# 7segmentDisplay.net
KiCad netlist of a schematic drawn in EAGLE
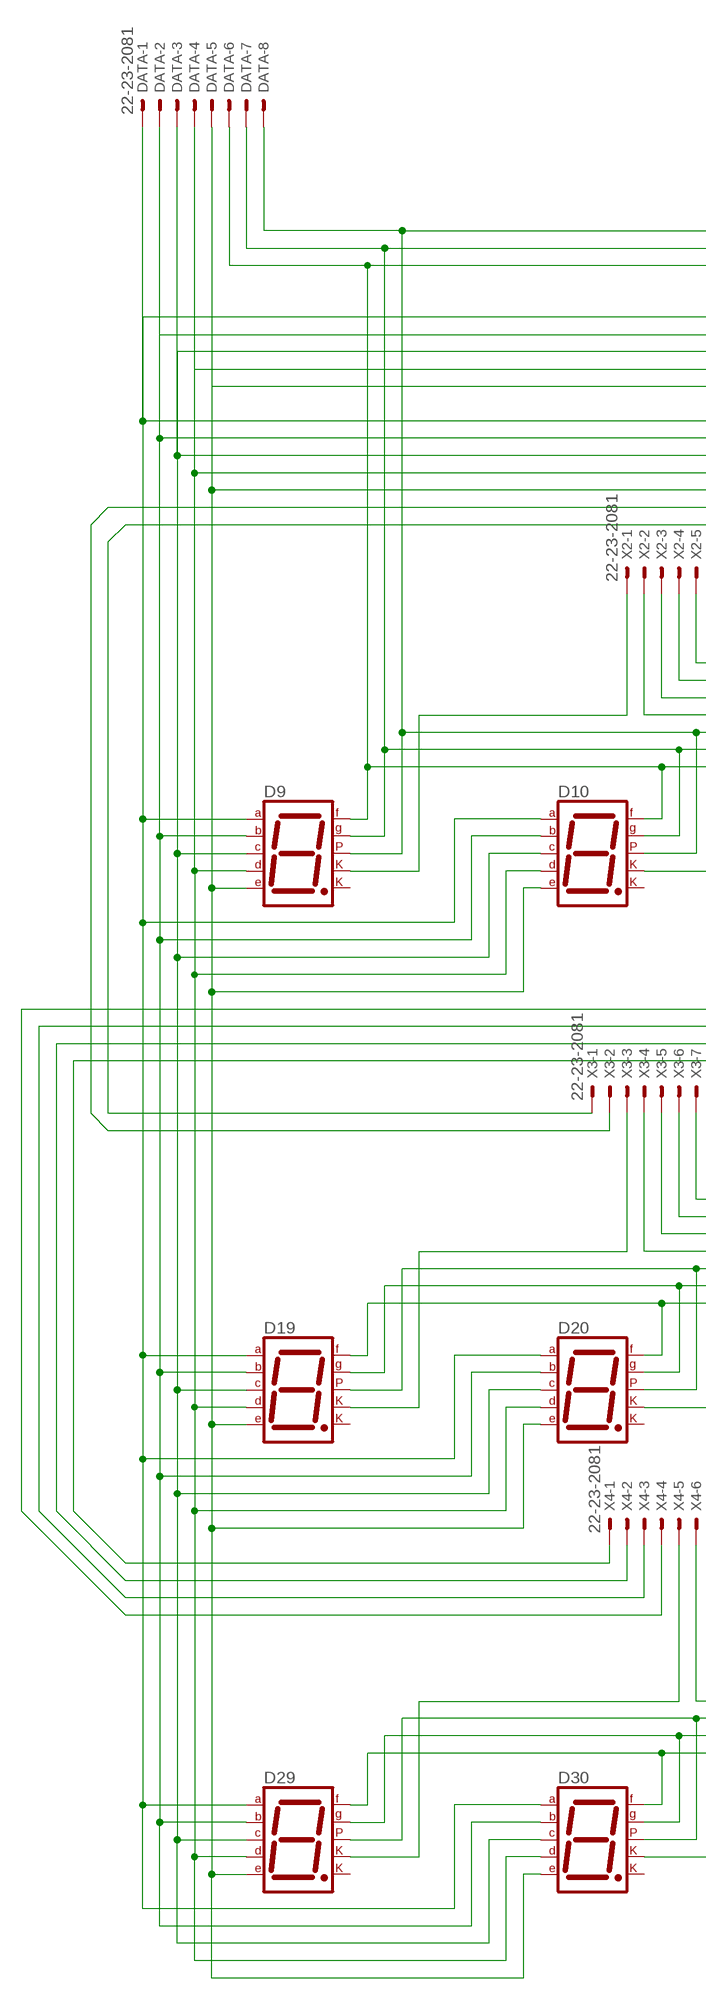
[diagram p0: schematic, sheet 1, part 1 of 2]
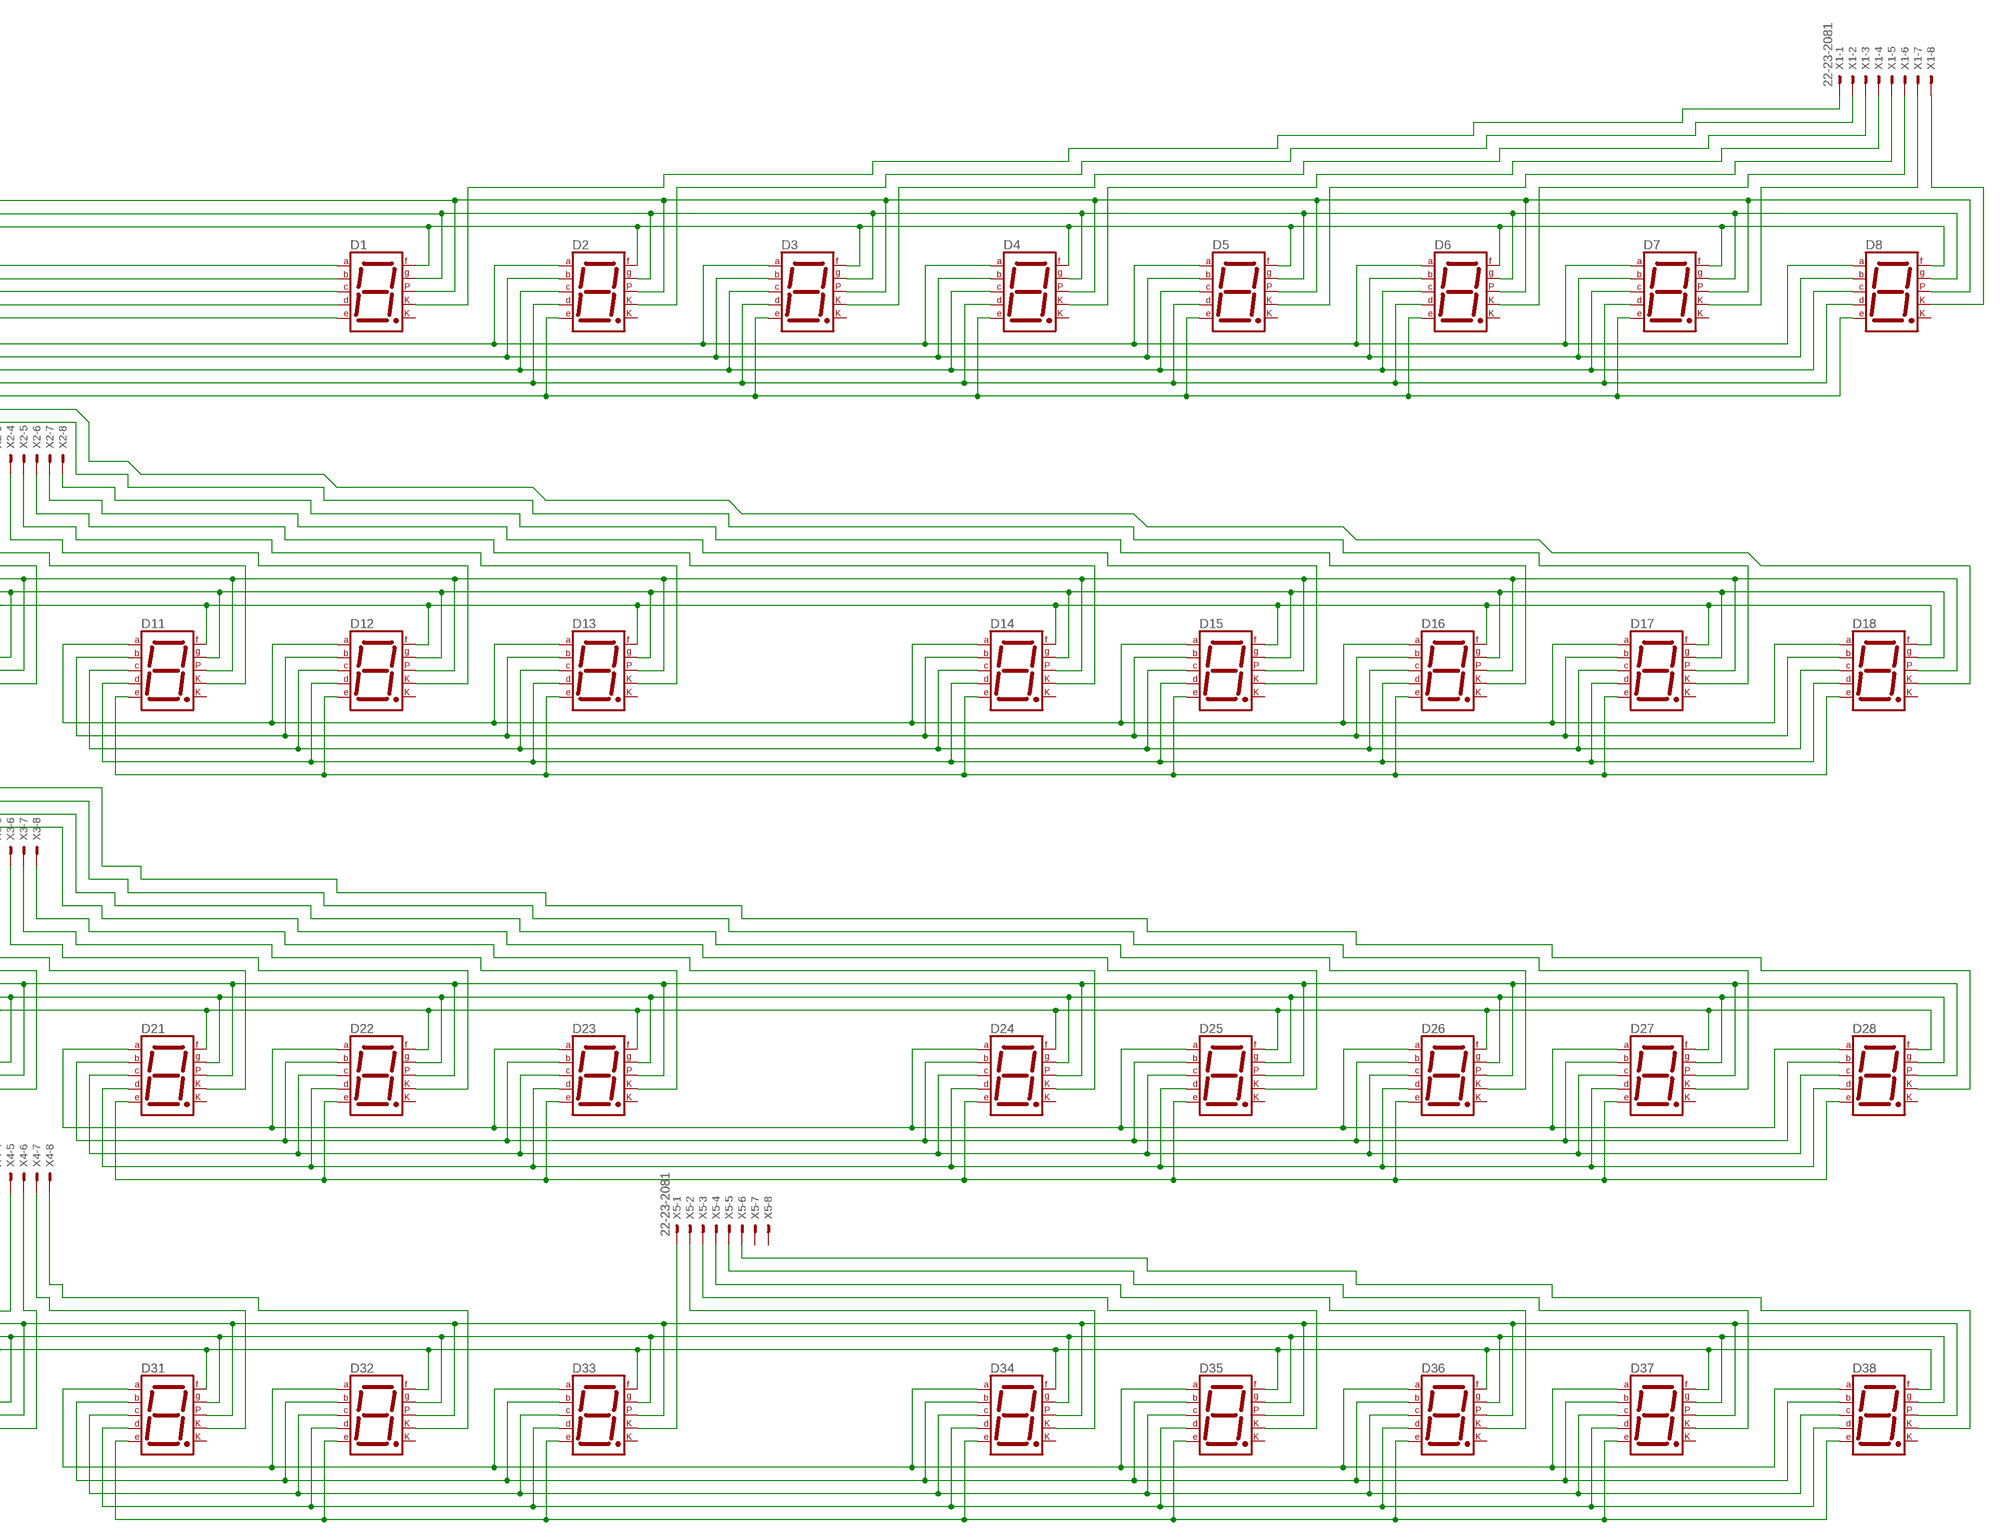
[diagram p1: schematic, sheet 1, part 2 of 2]

(export (version "E")
  (design (tool "Eeschema 10.0.6"))
  (components
    (comp (ref "D1")
      (value "7SEG-CK")
      (footprint "eagle-import:7SEG-13")
      (libsource (lib "eagle-import") (part "7SEG-CK"))
    )
    (comp (ref "D2")
      (value "7SEG-CK")
      (footprint "eagle-import:7SEG-13")
      (libsource (lib "eagle-import") (part "7SEG-CK"))
    )
    (comp (ref "D3")
      (value "7SEG-CK")
      (footprint "eagle-import:7SEG-13")
      (libsource (lib "eagle-import") (part "7SEG-CK"))
    )
    (comp (ref "D4")
      (value "7SEG-CK")
      (footprint "eagle-import:7SEG-13")
      (libsource (lib "eagle-import") (part "7SEG-CK"))
    )
    (comp (ref "D5")
      (value "7SEG-CK")
      (footprint "eagle-import:7SEG-13")
      (libsource (lib "eagle-import") (part "7SEG-CK"))
    )
    (comp (ref "D6")
      (value "7SEG-CK")
      (footprint "eagle-import:7SEG-13")
      (libsource (lib "eagle-import") (part "7SEG-CK"))
    )
    (comp (ref "D7")
      (value "7SEG-CK")
      (footprint "eagle-import:7SEG-13")
      (libsource (lib "eagle-import") (part "7SEG-CK"))
    )
    (comp (ref "D8")
      (value "7SEG-CK")
      (footprint "eagle-import:7SEG-13")
      (libsource (lib "eagle-import") (part "7SEG-CK"))
    )
    (comp (ref "D9")
      (value "7SEG-CK")
      (footprint "eagle-import:7SEG-13")
      (libsource (lib "eagle-import") (part "7SEG-CK"))
    )
    (comp (ref "D10")
      (value "7SEG-CK")
      (footprint "eagle-import:7SEG-13")
      (libsource (lib "eagle-import") (part "7SEG-CK"))
    )
    (comp (ref "D11")
      (value "7SEG-CK")
      (footprint "eagle-import:7SEG-13")
      (libsource (lib "eagle-import") (part "7SEG-CK"))
    )
    (comp (ref "D12")
      (value "7SEG-CK")
      (footprint "eagle-import:7SEG-13")
      (libsource (lib "eagle-import") (part "7SEG-CK"))
    )
    (comp (ref "D13")
      (value "7SEG-CK")
      (footprint "eagle-import:7SEG-13")
      (libsource (lib "eagle-import") (part "7SEG-CK"))
    )
    (comp (ref "D14")
      (value "7SEG-CK")
      (footprint "eagle-import:7SEG-13")
      (libsource (lib "eagle-import") (part "7SEG-CK"))
    )
    (comp (ref "D15")
      (value "7SEG-CK")
      (footprint "eagle-import:7SEG-13")
      (libsource (lib "eagle-import") (part "7SEG-CK"))
    )
    (comp (ref "D16")
      (value "7SEG-CK")
      (footprint "eagle-import:7SEG-13")
      (libsource (lib "eagle-import") (part "7SEG-CK"))
    )
    (comp (ref "D17")
      (value "7SEG-CK")
      (footprint "eagle-import:7SEG-13")
      (libsource (lib "eagle-import") (part "7SEG-CK"))
    )
    (comp (ref "D18")
      (value "7SEG-CK")
      (footprint "eagle-import:7SEG-13")
      (libsource (lib "eagle-import") (part "7SEG-CK"))
    )
    (comp (ref "D19")
      (value "7SEG-CK")
      (footprint "eagle-import:7SEG-13")
      (libsource (lib "eagle-import") (part "7SEG-CK"))
    )
    (comp (ref "D20")
      (value "7SEG-CK")
      (footprint "eagle-import:7SEG-13")
      (libsource (lib "eagle-import") (part "7SEG-CK"))
    )
    (comp (ref "D21")
      (value "7SEG-CK")
      (footprint "eagle-import:7SEG-13")
      (libsource (lib "eagle-import") (part "7SEG-CK"))
    )
    (comp (ref "D22")
      (value "7SEG-CK")
      (footprint "eagle-import:7SEG-13")
      (libsource (lib "eagle-import") (part "7SEG-CK"))
    )
    (comp (ref "D23")
      (value "7SEG-CK")
      (footprint "eagle-import:7SEG-13")
      (libsource (lib "eagle-import") (part "7SEG-CK"))
    )
    (comp (ref "D24")
      (value "7SEG-CK")
      (footprint "eagle-import:7SEG-13")
      (libsource (lib "eagle-import") (part "7SEG-CK"))
    )
    (comp (ref "D25")
      (value "7SEG-CK")
      (footprint "eagle-import:7SEG-13")
      (libsource (lib "eagle-import") (part "7SEG-CK"))
    )
    (comp (ref "D26")
      (value "7SEG-CK")
      (footprint "eagle-import:7SEG-13")
      (libsource (lib "eagle-import") (part "7SEG-CK"))
    )
    (comp (ref "D27")
      (value "7SEG-CK")
      (footprint "eagle-import:7SEG-13")
      (libsource (lib "eagle-import") (part "7SEG-CK"))
    )
    (comp (ref "D28")
      (value "7SEG-CK")
      (footprint "eagle-import:7SEG-13")
      (libsource (lib "eagle-import") (part "7SEG-CK"))
    )
    (comp (ref "D29")
      (value "7SEG-CK")
      (footprint "eagle-import:7SEG-13")
      (libsource (lib "eagle-import") (part "7SEG-CK"))
    )
    (comp (ref "D30")
      (value "7SEG-CK")
      (footprint "eagle-import:7SEG-13")
      (libsource (lib "eagle-import") (part "7SEG-CK"))
    )
    (comp (ref "D31")
      (value "7SEG-CK")
      (footprint "eagle-import:7SEG-13")
      (libsource (lib "eagle-import") (part "7SEG-CK"))
    )
    (comp (ref "D32")
      (value "7SEG-CK")
      (footprint "eagle-import:7SEG-13")
      (libsource (lib "eagle-import") (part "7SEG-CK"))
    )
    (comp (ref "D33")
      (value "7SEG-CK")
      (footprint "eagle-import:7SEG-13")
      (libsource (lib "eagle-import") (part "7SEG-CK"))
    )
    (comp (ref "D34")
      (value "7SEG-CK")
      (footprint "eagle-import:7SEG-13")
      (libsource (lib "eagle-import") (part "7SEG-CK"))
    )
    (comp (ref "D35")
      (value "7SEG-CK")
      (footprint "eagle-import:7SEG-13")
      (libsource (lib "eagle-import") (part "7SEG-CK"))
    )
    (comp (ref "D36")
      (value "7SEG-CK")
      (footprint "eagle-import:7SEG-13")
      (libsource (lib "eagle-import") (part "7SEG-CK"))
    )
    (comp (ref "D37")
      (value "7SEG-CK")
      (footprint "eagle-import:7SEG-13")
      (libsource (lib "eagle-import") (part "7SEG-CK"))
    )
    (comp (ref "D38")
      (value "7SEG-CK")
      (footprint "eagle-import:7SEG-13")
      (libsource (lib "eagle-import") (part "7SEG-CK"))
    )
    (comp (ref "DATA")
      (value "22-23-2081")
      (footprint "eagle-import:22-23-2081")
      (fields (field (name "MF") "MOLEX"))
      (libsource (lib "eagle-import") (part "22-23-2081"))
    )
    (comp (ref "X1")
      (value "22-23-2081")
      (footprint "eagle-import:22-23-2081")
      (fields (field (name "MF") "MOLEX"))
      (libsource (lib "eagle-import") (part "22-23-2081"))
    )
    (comp (ref "X2")
      (value "22-23-2081")
      (footprint "eagle-import:22-23-2081")
      (fields (field (name "MF") "MOLEX"))
      (libsource (lib "eagle-import") (part "22-23-2081"))
    )
    (comp (ref "X3")
      (value "22-23-2081")
      (footprint "eagle-import:22-23-2081")
      (fields (field (name "MF") "MOLEX"))
      (libsource (lib "eagle-import") (part "22-23-2081"))
    )
    (comp (ref "X4")
      (value "22-23-2081")
      (footprint "eagle-import:22-23-2081")
      (fields (field (name "MF") "MOLEX"))
      (libsource (lib "eagle-import") (part "22-23-2081"))
    )
    (comp (ref "X5")
      (value "22-23-2081")
      (footprint "eagle-import:22-23-2081")
      (fields (field (name "MF") "MOLEX"))
      (libsource (lib "eagle-import") (part "22-23-2081"))
    )
  )
  (nets
    (net (code "1") (name "Net-(D1-A)") (class "Default")
      (node (ref "D1") (pin "7") (pinfunction "A_7") (pintype "passive"))
      (node (ref "D10") (pin "7") (pinfunction "A_7") (pintype "passive"))
      (node (ref "D19") (pin "7") (pinfunction "A_7") (pintype "passive"))
      (node (ref "D2") (pin "7") (pinfunction "A_7") (pintype "passive"))
      (node (ref "D20") (pin "7") (pinfunction "A_7") (pintype "passive"))
      (node (ref "D29") (pin "7") (pinfunction "A_7") (pintype "passive"))
      (node (ref "D3") (pin "7") (pinfunction "A_7") (pintype "passive"))
      (node (ref "D30") (pin "7") (pinfunction "A_7") (pintype "passive"))
      (node (ref "D4") (pin "7") (pinfunction "A_7") (pintype "passive"))
      (node (ref "D5") (pin "7") (pinfunction "A_7") (pintype "passive"))
      (node (ref "D6") (pin "7") (pinfunction "A_7") (pintype "passive"))
      (node (ref "D7") (pin "7") (pinfunction "A_7") (pintype "passive"))
      (node (ref "D8") (pin "7") (pinfunction "A_7") (pintype "passive"))
      (node (ref "D9") (pin "7") (pinfunction "A_7") (pintype "passive"))
      (node (ref "DATA") (pin "1") (pinfunction "S_1") (pintype "passive"))
    )
    (net (code "2") (name "Net-(D1-B)") (class "Default")
      (node (ref "D1") (pin "6") (pinfunction "B_6") (pintype "passive"))
      (node (ref "D10") (pin "6") (pinfunction "B_6") (pintype "passive"))
      (node (ref "D19") (pin "6") (pinfunction "B_6") (pintype "passive"))
      (node (ref "D2") (pin "6") (pinfunction "B_6") (pintype "passive"))
      (node (ref "D20") (pin "6") (pinfunction "B_6") (pintype "passive"))
      (node (ref "D29") (pin "6") (pinfunction "B_6") (pintype "passive"))
      (node (ref "D3") (pin "6") (pinfunction "B_6") (pintype "passive"))
      (node (ref "D30") (pin "6") (pinfunction "B_6") (pintype "passive"))
      (node (ref "D4") (pin "6") (pinfunction "B_6") (pintype "passive"))
      (node (ref "D5") (pin "6") (pinfunction "B_6") (pintype "passive"))
      (node (ref "D6") (pin "6") (pinfunction "B_6") (pintype "passive"))
      (node (ref "D7") (pin "6") (pinfunction "B_6") (pintype "passive"))
      (node (ref "D8") (pin "6") (pinfunction "B_6") (pintype "passive"))
      (node (ref "D9") (pin "6") (pinfunction "B_6") (pintype "passive"))
      (node (ref "DATA") (pin "2") (pinfunction "S_2") (pintype "passive"))
    )
    (net (code "3") (name "Net-(D1-C)") (class "Default")
      (node (ref "D1") (pin "4") (pinfunction "C_4") (pintype "passive"))
      (node (ref "D10") (pin "4") (pinfunction "C_4") (pintype "passive"))
      (node (ref "D19") (pin "4") (pinfunction "C_4") (pintype "passive"))
      (node (ref "D2") (pin "4") (pinfunction "C_4") (pintype "passive"))
      (node (ref "D20") (pin "4") (pinfunction "C_4") (pintype "passive"))
      (node (ref "D29") (pin "4") (pinfunction "C_4") (pintype "passive"))
      (node (ref "D3") (pin "4") (pinfunction "C_4") (pintype "passive"))
      (node (ref "D30") (pin "4") (pinfunction "C_4") (pintype "passive"))
      (node (ref "D4") (pin "4") (pinfunction "C_4") (pintype "passive"))
      (node (ref "D5") (pin "4") (pinfunction "C_4") (pintype "passive"))
      (node (ref "D6") (pin "4") (pinfunction "C_4") (pintype "passive"))
      (node (ref "D7") (pin "4") (pinfunction "C_4") (pintype "passive"))
      (node (ref "D8") (pin "4") (pinfunction "C_4") (pintype "passive"))
      (node (ref "D9") (pin "4") (pinfunction "C_4") (pintype "passive"))
      (node (ref "DATA") (pin "3") (pinfunction "S_3") (pintype "passive"))
    )
    (net (code "4") (name "Net-(D1-CK1)") (class "Default")
      (node (ref "D1") (pin "3") (pinfunction "CK1_3") (pintype "passive"))
      (node (ref "X1") (pin "1") (pinfunction "S_1") (pintype "passive"))
    )
    (net (code "5") (name "Net-(D1-D)") (class "Default")
      (node (ref "D1") (pin "2") (pinfunction "D_2") (pintype "passive"))
      (node (ref "D10") (pin "2") (pinfunction "D_2") (pintype "passive"))
      (node (ref "D19") (pin "2") (pinfunction "D_2") (pintype "passive"))
      (node (ref "D2") (pin "2") (pinfunction "D_2") (pintype "passive"))
      (node (ref "D20") (pin "2") (pinfunction "D_2") (pintype "passive"))
      (node (ref "D29") (pin "2") (pinfunction "D_2") (pintype "passive"))
      (node (ref "D3") (pin "2") (pinfunction "D_2") (pintype "passive"))
      (node (ref "D30") (pin "2") (pinfunction "D_2") (pintype "passive"))
      (node (ref "D4") (pin "2") (pinfunction "D_2") (pintype "passive"))
      (node (ref "D5") (pin "2") (pinfunction "D_2") (pintype "passive"))
      (node (ref "D6") (pin "2") (pinfunction "D_2") (pintype "passive"))
      (node (ref "D7") (pin "2") (pinfunction "D_2") (pintype "passive"))
      (node (ref "D8") (pin "2") (pinfunction "D_2") (pintype "passive"))
      (node (ref "D9") (pin "2") (pinfunction "D_2") (pintype "passive"))
      (node (ref "DATA") (pin "4") (pinfunction "S_4") (pintype "passive"))
    )
    (net (code "6") (name "Net-(D1-DP)") (class "Default")
      (node (ref "D1") (pin "5") (pinfunction "DP_5") (pintype "passive"))
      (node (ref "D10") (pin "5") (pinfunction "DP_5") (pintype "passive"))
      (node (ref "D11") (pin "5") (pinfunction "DP_5") (pintype "passive"))
      (node (ref "D12") (pin "5") (pinfunction "DP_5") (pintype "passive"))
      (node (ref "D13") (pin "5") (pinfunction "DP_5") (pintype "passive"))
      (node (ref "D14") (pin "5") (pinfunction "DP_5") (pintype "passive"))
      (node (ref "D15") (pin "5") (pinfunction "DP_5") (pintype "passive"))
      (node (ref "D16") (pin "5") (pinfunction "DP_5") (pintype "passive"))
      (node (ref "D17") (pin "5") (pinfunction "DP_5") (pintype "passive"))
      (node (ref "D18") (pin "5") (pinfunction "DP_5") (pintype "passive"))
      (node (ref "D2") (pin "5") (pinfunction "DP_5") (pintype "passive"))
      (node (ref "D3") (pin "5") (pinfunction "DP_5") (pintype "passive"))
      (node (ref "D4") (pin "5") (pinfunction "DP_5") (pintype "passive"))
      (node (ref "D5") (pin "5") (pinfunction "DP_5") (pintype "passive"))
      (node (ref "D6") (pin "5") (pinfunction "DP_5") (pintype "passive"))
      (node (ref "D7") (pin "5") (pinfunction "DP_5") (pintype "passive"))
      (node (ref "D8") (pin "5") (pinfunction "DP_5") (pintype "passive"))
      (node (ref "D9") (pin "5") (pinfunction "DP_5") (pintype "passive"))
      (node (ref "DATA") (pin "8") (pinfunction "S_8") (pintype "passive"))
    )
    (net (code "7") (name "Net-(D1-E)") (class "Default")
      (node (ref "D1") (pin "1") (pinfunction "E_1") (pintype "passive"))
      (node (ref "D10") (pin "1") (pinfunction "E_1") (pintype "passive"))
      (node (ref "D19") (pin "1") (pinfunction "E_1") (pintype "passive"))
      (node (ref "D2") (pin "1") (pinfunction "E_1") (pintype "passive"))
      (node (ref "D20") (pin "1") (pinfunction "E_1") (pintype "passive"))
      (node (ref "D29") (pin "1") (pinfunction "E_1") (pintype "passive"))
      (node (ref "D3") (pin "1") (pinfunction "E_1") (pintype "passive"))
      (node (ref "D30") (pin "1") (pinfunction "E_1") (pintype "passive"))
      (node (ref "D4") (pin "1") (pinfunction "E_1") (pintype "passive"))
      (node (ref "D5") (pin "1") (pinfunction "E_1") (pintype "passive"))
      (node (ref "D6") (pin "1") (pinfunction "E_1") (pintype "passive"))
      (node (ref "D7") (pin "1") (pinfunction "E_1") (pintype "passive"))
      (node (ref "D8") (pin "1") (pinfunction "E_1") (pintype "passive"))
      (node (ref "D9") (pin "1") (pinfunction "E_1") (pintype "passive"))
      (node (ref "DATA") (pin "5") (pinfunction "S_5") (pintype "passive"))
    )
    (net (code "8") (name "Net-(D1-F)") (class "Default")
      (node (ref "D1") (pin "9") (pinfunction "F_9") (pintype "passive"))
      (node (ref "D10") (pin "9") (pinfunction "F_9") (pintype "passive"))
      (node (ref "D11") (pin "9") (pinfunction "F_9") (pintype "passive"))
      (node (ref "D12") (pin "9") (pinfunction "F_9") (pintype "passive"))
      (node (ref "D13") (pin "9") (pinfunction "F_9") (pintype "passive"))
      (node (ref "D14") (pin "9") (pinfunction "F_9") (pintype "passive"))
      (node (ref "D15") (pin "9") (pinfunction "F_9") (pintype "passive"))
      (node (ref "D16") (pin "9") (pinfunction "F_9") (pintype "passive"))
      (node (ref "D17") (pin "9") (pinfunction "F_9") (pintype "passive"))
      (node (ref "D18") (pin "9") (pinfunction "F_9") (pintype "passive"))
      (node (ref "D2") (pin "9") (pinfunction "F_9") (pintype "passive"))
      (node (ref "D3") (pin "9") (pinfunction "F_9") (pintype "passive"))
      (node (ref "D4") (pin "9") (pinfunction "F_9") (pintype "passive"))
      (node (ref "D5") (pin "9") (pinfunction "F_9") (pintype "passive"))
      (node (ref "D6") (pin "9") (pinfunction "F_9") (pintype "passive"))
      (node (ref "D7") (pin "9") (pinfunction "F_9") (pintype "passive"))
      (node (ref "D8") (pin "9") (pinfunction "F_9") (pintype "passive"))
      (node (ref "D9") (pin "9") (pinfunction "F_9") (pintype "passive"))
      (node (ref "DATA") (pin "6") (pinfunction "S_6") (pintype "passive"))
    )
    (net (code "9") (name "Net-(D1-G)") (class "Default")
      (node (ref "D1") (pin "10") (pinfunction "G_10") (pintype "passive"))
      (node (ref "D10") (pin "10") (pinfunction "G_10") (pintype "passive"))
      (node (ref "D11") (pin "10") (pinfunction "G_10") (pintype "passive"))
      (node (ref "D12") (pin "10") (pinfunction "G_10") (pintype "passive"))
      (node (ref "D13") (pin "10") (pinfunction "G_10") (pintype "passive"))
      (node (ref "D2") (pin "10") (pinfunction "G_10") (pintype "passive"))
      (node (ref "D3") (pin "10") (pinfunction "G_10") (pintype "passive"))
      (node (ref "D4") (pin "10") (pinfunction "G_10") (pintype "passive"))
      (node (ref "D5") (pin "10") (pinfunction "G_10") (pintype "passive"))
      (node (ref "D6") (pin "10") (pinfunction "G_10") (pintype "passive"))
      (node (ref "D7") (pin "10") (pinfunction "G_10") (pintype "passive"))
      (node (ref "D8") (pin "10") (pinfunction "G_10") (pintype "passive"))
      (node (ref "D9") (pin "10") (pinfunction "G_10") (pintype "passive"))
      (node (ref "DATA") (pin "7") (pinfunction "S_7") (pintype "passive"))
    )
    (net (code "10") (name "Net-(D2-CK1)") (class "Default")
      (node (ref "D2") (pin "3") (pinfunction "CK1_3") (pintype "passive"))
      (node (ref "X1") (pin "2") (pinfunction "S_2") (pintype "passive"))
    )
    (net (code "11") (name "Net-(D3-CK1)") (class "Default")
      (node (ref "D3") (pin "3") (pinfunction "CK1_3") (pintype "passive"))
      (node (ref "X1") (pin "3") (pinfunction "S_3") (pintype "passive"))
    )
    (net (code "12") (name "Net-(D4-CK1)") (class "Default")
      (node (ref "D4") (pin "3") (pinfunction "CK1_3") (pintype "passive"))
      (node (ref "X1") (pin "4") (pinfunction "S_4") (pintype "passive"))
    )
    (net (code "13") (name "Net-(D5-CK1)") (class "Default")
      (node (ref "D5") (pin "3") (pinfunction "CK1_3") (pintype "passive"))
      (node (ref "X1") (pin "5") (pinfunction "S_5") (pintype "passive"))
    )
    (net (code "14") (name "Net-(D6-CK1)") (class "Default")
      (node (ref "D6") (pin "3") (pinfunction "CK1_3") (pintype "passive"))
      (node (ref "X1") (pin "6") (pinfunction "S_6") (pintype "passive"))
    )
    (net (code "15") (name "Net-(D7-CK1)") (class "Default")
      (node (ref "D7") (pin "3") (pinfunction "CK1_3") (pintype "passive"))
      (node (ref "X1") (pin "7") (pinfunction "S_7") (pintype "passive"))
    )
    (net (code "16") (name "Net-(D8-CK1)") (class "Default")
      (node (ref "D8") (pin "3") (pinfunction "CK1_3") (pintype "passive"))
      (node (ref "X1") (pin "8") (pinfunction "S_8") (pintype "passive"))
    )
    (net (code "17") (name "Net-(D9-CK1)") (class "Default")
      (node (ref "D9") (pin "3") (pinfunction "CK1_3") (pintype "passive"))
      (node (ref "X2") (pin "1") (pinfunction "S_1") (pintype "passive"))
    )
    (net (code "18") (name "Net-(D10-CK1)") (class "Default")
      (node (ref "D10") (pin "3") (pinfunction "CK1_3") (pintype "passive"))
      (node (ref "X2") (pin "2") (pinfunction "S_2") (pintype "passive"))
    )
    (net (code "19") (name "Net-(D11-A)") (class "Default")
      (node (ref "D11") (pin "7") (pinfunction "A_7") (pintype "passive"))
      (node (ref "D12") (pin "7") (pinfunction "A_7") (pintype "passive"))
      (node (ref "D13") (pin "7") (pinfunction "A_7") (pintype "passive"))
    )
    (net (code "20") (name "Net-(D11-B)") (class "Default")
      (node (ref "D11") (pin "6") (pinfunction "B_6") (pintype "passive"))
      (node (ref "D12") (pin "6") (pinfunction "B_6") (pintype "passive"))
      (node (ref "D13") (pin "6") (pinfunction "B_6") (pintype "passive"))
    )
    (net (code "21") (name "Net-(D11-C)") (class "Default")
      (node (ref "D11") (pin "4") (pinfunction "C_4") (pintype "passive"))
      (node (ref "D12") (pin "4") (pinfunction "C_4") (pintype "passive"))
      (node (ref "D13") (pin "4") (pinfunction "C_4") (pintype "passive"))
    )
    (net (code "22") (name "Net-(D11-CK1)") (class "Default")
      (node (ref "D11") (pin "3") (pinfunction "CK1_3") (pintype "passive"))
      (node (ref "X2") (pin "3") (pinfunction "S_3") (pintype "passive"))
    )
    (net (code "23") (name "Net-(D11-D)") (class "Default")
      (node (ref "D11") (pin "2") (pinfunction "D_2") (pintype "passive"))
      (node (ref "D12") (pin "2") (pinfunction "D_2") (pintype "passive"))
      (node (ref "D13") (pin "2") (pinfunction "D_2") (pintype "passive"))
    )
    (net (code "24") (name "Net-(D11-E)") (class "Default")
      (node (ref "D11") (pin "1") (pinfunction "E_1") (pintype "passive"))
      (node (ref "D12") (pin "1") (pinfunction "E_1") (pintype "passive"))
      (node (ref "D13") (pin "1") (pinfunction "E_1") (pintype "passive"))
    )
    (net (code "25") (name "Net-(D12-CK1)") (class "Default")
      (node (ref "D12") (pin "3") (pinfunction "CK1_3") (pintype "passive"))
      (node (ref "X2") (pin "4") (pinfunction "S_4") (pintype "passive"))
    )
    (net (code "26") (name "Net-(D13-CK1)") (class "Default")
      (node (ref "D13") (pin "3") (pinfunction "CK1_3") (pintype "passive"))
      (node (ref "X2") (pin "5") (pinfunction "S_5") (pintype "passive"))
    )
    (net (code "27") (name "Net-(D14-A)") (class "Default")
      (node (ref "D14") (pin "7") (pinfunction "A_7") (pintype "passive"))
      (node (ref "D15") (pin "7") (pinfunction "A_7") (pintype "passive"))
      (node (ref "D16") (pin "7") (pinfunction "A_7") (pintype "passive"))
      (node (ref "D17") (pin "7") (pinfunction "A_7") (pintype "passive"))
      (node (ref "D18") (pin "7") (pinfunction "A_7") (pintype "passive"))
    )
    (net (code "28") (name "Net-(D14-B)") (class "Default")
      (node (ref "D14") (pin "6") (pinfunction "B_6") (pintype "passive"))
      (node (ref "D15") (pin "6") (pinfunction "B_6") (pintype "passive"))
      (node (ref "D16") (pin "6") (pinfunction "B_6") (pintype "passive"))
      (node (ref "D17") (pin "6") (pinfunction "B_6") (pintype "passive"))
      (node (ref "D18") (pin "6") (pinfunction "B_6") (pintype "passive"))
    )
    (net (code "29") (name "Net-(D14-C)") (class "Default")
      (node (ref "D14") (pin "4") (pinfunction "C_4") (pintype "passive"))
      (node (ref "D15") (pin "4") (pinfunction "C_4") (pintype "passive"))
      (node (ref "D16") (pin "4") (pinfunction "C_4") (pintype "passive"))
      (node (ref "D17") (pin "4") (pinfunction "C_4") (pintype "passive"))
      (node (ref "D18") (pin "4") (pinfunction "C_4") (pintype "passive"))
    )
    (net (code "30") (name "Net-(D14-CK1)") (class "Default")
      (node (ref "D14") (pin "3") (pinfunction "CK1_3") (pintype "passive"))
      (node (ref "X2") (pin "6") (pinfunction "S_6") (pintype "passive"))
    )
    (net (code "31") (name "Net-(D14-D)") (class "Default")
      (node (ref "D14") (pin "2") (pinfunction "D_2") (pintype "passive"))
      (node (ref "D15") (pin "2") (pinfunction "D_2") (pintype "passive"))
      (node (ref "D16") (pin "2") (pinfunction "D_2") (pintype "passive"))
      (node (ref "D17") (pin "2") (pinfunction "D_2") (pintype "passive"))
      (node (ref "D18") (pin "2") (pinfunction "D_2") (pintype "passive"))
    )
    (net (code "32") (name "Net-(D14-E)") (class "Default")
      (node (ref "D14") (pin "1") (pinfunction "E_1") (pintype "passive"))
      (node (ref "D15") (pin "1") (pinfunction "E_1") (pintype "passive"))
      (node (ref "D16") (pin "1") (pinfunction "E_1") (pintype "passive"))
      (node (ref "D17") (pin "1") (pinfunction "E_1") (pintype "passive"))
      (node (ref "D18") (pin "1") (pinfunction "E_1") (pintype "passive"))
    )
    (net (code "33") (name "Net-(D14-G)") (class "Default")
      (node (ref "D14") (pin "10") (pinfunction "G_10") (pintype "passive"))
      (node (ref "D15") (pin "10") (pinfunction "G_10") (pintype "passive"))
      (node (ref "D16") (pin "10") (pinfunction "G_10") (pintype "passive"))
      (node (ref "D17") (pin "10") (pinfunction "G_10") (pintype "passive"))
      (node (ref "D18") (pin "10") (pinfunction "G_10") (pintype "passive"))
    )
    (net (code "34") (name "Net-(D15-CK1)") (class "Default")
      (node (ref "D15") (pin "3") (pinfunction "CK1_3") (pintype "passive"))
      (node (ref "X2") (pin "7") (pinfunction "S_7") (pintype "passive"))
    )
    (net (code "35") (name "Net-(D16-CK1)") (class "Default")
      (node (ref "D16") (pin "3") (pinfunction "CK1_3") (pintype "passive"))
      (node (ref "X2") (pin "8") (pinfunction "S_8") (pintype "passive"))
    )
    (net (code "36") (name "Net-(D17-CK1)") (class "Default")
      (node (ref "D17") (pin "3") (pinfunction "CK1_3") (pintype "passive"))
      (node (ref "X3") (pin "1") (pinfunction "S_1") (pintype "passive"))
    )
    (net (code "37") (name "Net-(D18-CK1)") (class "Default")
      (node (ref "D18") (pin "3") (pinfunction "CK1_3") (pintype "passive"))
      (node (ref "X3") (pin "2") (pinfunction "S_2") (pintype "passive"))
    )
    (net (code "38") (name "Net-(D19-CK1)") (class "Default")
      (node (ref "D19") (pin "3") (pinfunction "CK1_3") (pintype "passive"))
      (node (ref "X3") (pin "3") (pinfunction "S_3") (pintype "passive"))
    )
    (net (code "39") (name "Net-(D19-DP)") (class "Default")
      (node (ref "D19") (pin "5") (pinfunction "DP_5") (pintype "passive"))
      (node (ref "D20") (pin "5") (pinfunction "DP_5") (pintype "passive"))
      (node (ref "D21") (pin "5") (pinfunction "DP_5") (pintype "passive"))
      (node (ref "D22") (pin "5") (pinfunction "DP_5") (pintype "passive"))
      (node (ref "D23") (pin "5") (pinfunction "DP_5") (pintype "passive"))
      (node (ref "D24") (pin "5") (pinfunction "DP_5") (pintype "passive"))
      (node (ref "D25") (pin "5") (pinfunction "DP_5") (pintype "passive"))
      (node (ref "D26") (pin "5") (pinfunction "DP_5") (pintype "passive"))
      (node (ref "D27") (pin "5") (pinfunction "DP_5") (pintype "passive"))
      (node (ref "D28") (pin "5") (pinfunction "DP_5") (pintype "passive"))
    )
    (net (code "40") (name "Net-(D19-F)") (class "Default")
      (node (ref "D19") (pin "9") (pinfunction "F_9") (pintype "passive"))
      (node (ref "D20") (pin "9") (pinfunction "F_9") (pintype "passive"))
      (node (ref "D21") (pin "9") (pinfunction "F_9") (pintype "passive"))
      (node (ref "D22") (pin "9") (pinfunction "F_9") (pintype "passive"))
      (node (ref "D23") (pin "9") (pinfunction "F_9") (pintype "passive"))
      (node (ref "D24") (pin "9") (pinfunction "F_9") (pintype "passive"))
      (node (ref "D25") (pin "9") (pinfunction "F_9") (pintype "passive"))
      (node (ref "D26") (pin "9") (pinfunction "F_9") (pintype "passive"))
      (node (ref "D27") (pin "9") (pinfunction "F_9") (pintype "passive"))
      (node (ref "D28") (pin "9") (pinfunction "F_9") (pintype "passive"))
    )
    (net (code "41") (name "Net-(D19-G)") (class "Default")
      (node (ref "D19") (pin "10") (pinfunction "G_10") (pintype "passive"))
      (node (ref "D20") (pin "10") (pinfunction "G_10") (pintype "passive"))
      (node (ref "D21") (pin "10") (pinfunction "G_10") (pintype "passive"))
      (node (ref "D22") (pin "10") (pinfunction "G_10") (pintype "passive"))
      (node (ref "D23") (pin "10") (pinfunction "G_10") (pintype "passive"))
    )
    (net (code "42") (name "Net-(D20-CK1)") (class "Default")
      (node (ref "D20") (pin "3") (pinfunction "CK1_3") (pintype "passive"))
      (node (ref "X3") (pin "4") (pinfunction "S_4") (pintype "passive"))
    )
    (net (code "43") (name "Net-(D21-A)") (class "Default")
      (node (ref "D21") (pin "7") (pinfunction "A_7") (pintype "passive"))
      (node (ref "D22") (pin "7") (pinfunction "A_7") (pintype "passive"))
      (node (ref "D23") (pin "7") (pinfunction "A_7") (pintype "passive"))
    )
    (net (code "44") (name "Net-(D21-B)") (class "Default")
      (node (ref "D21") (pin "6") (pinfunction "B_6") (pintype "passive"))
      (node (ref "D22") (pin "6") (pinfunction "B_6") (pintype "passive"))
      (node (ref "D23") (pin "6") (pinfunction "B_6") (pintype "passive"))
    )
    (net (code "45") (name "Net-(D21-C)") (class "Default")
      (node (ref "D21") (pin "4") (pinfunction "C_4") (pintype "passive"))
      (node (ref "D22") (pin "4") (pinfunction "C_4") (pintype "passive"))
      (node (ref "D23") (pin "4") (pinfunction "C_4") (pintype "passive"))
    )
    (net (code "46") (name "Net-(D21-CK1)") (class "Default")
      (node (ref "D21") (pin "3") (pinfunction "CK1_3") (pintype "passive"))
      (node (ref "X3") (pin "5") (pinfunction "S_5") (pintype "passive"))
    )
    (net (code "47") (name "Net-(D21-D)") (class "Default")
      (node (ref "D21") (pin "2") (pinfunction "D_2") (pintype "passive"))
      (node (ref "D22") (pin "2") (pinfunction "D_2") (pintype "passive"))
      (node (ref "D23") (pin "2") (pinfunction "D_2") (pintype "passive"))
    )
    (net (code "48") (name "Net-(D21-E)") (class "Default")
      (node (ref "D21") (pin "1") (pinfunction "E_1") (pintype "passive"))
      (node (ref "D22") (pin "1") (pinfunction "E_1") (pintype "passive"))
      (node (ref "D23") (pin "1") (pinfunction "E_1") (pintype "passive"))
    )
    (net (code "49") (name "Net-(D22-CK1)") (class "Default")
      (node (ref "D22") (pin "3") (pinfunction "CK1_3") (pintype "passive"))
      (node (ref "X3") (pin "6") (pinfunction "S_6") (pintype "passive"))
    )
    (net (code "50") (name "Net-(D23-CK1)") (class "Default")
      (node (ref "D23") (pin "3") (pinfunction "CK1_3") (pintype "passive"))
      (node (ref "X3") (pin "7") (pinfunction "S_7") (pintype "passive"))
    )
    (net (code "51") (name "Net-(D24-A)") (class "Default")
      (node (ref "D24") (pin "7") (pinfunction "A_7") (pintype "passive"))
      (node (ref "D25") (pin "7") (pinfunction "A_7") (pintype "passive"))
      (node (ref "D26") (pin "7") (pinfunction "A_7") (pintype "passive"))
      (node (ref "D27") (pin "7") (pinfunction "A_7") (pintype "passive"))
      (node (ref "D28") (pin "7") (pinfunction "A_7") (pintype "passive"))
    )
    (net (code "52") (name "Net-(D24-B)") (class "Default")
      (node (ref "D24") (pin "6") (pinfunction "B_6") (pintype "passive"))
      (node (ref "D25") (pin "6") (pinfunction "B_6") (pintype "passive"))
      (node (ref "D26") (pin "6") (pinfunction "B_6") (pintype "passive"))
      (node (ref "D27") (pin "6") (pinfunction "B_6") (pintype "passive"))
      (node (ref "D28") (pin "6") (pinfunction "B_6") (pintype "passive"))
    )
    (net (code "53") (name "Net-(D24-C)") (class "Default")
      (node (ref "D24") (pin "4") (pinfunction "C_4") (pintype "passive"))
      (node (ref "D25") (pin "4") (pinfunction "C_4") (pintype "passive"))
      (node (ref "D26") (pin "4") (pinfunction "C_4") (pintype "passive"))
      (node (ref "D27") (pin "4") (pinfunction "C_4") (pintype "passive"))
      (node (ref "D28") (pin "4") (pinfunction "C_4") (pintype "passive"))
    )
    (net (code "54") (name "Net-(D24-CK1)") (class "Default")
      (node (ref "D24") (pin "3") (pinfunction "CK1_3") (pintype "passive"))
      (node (ref "X3") (pin "8") (pinfunction "S_8") (pintype "passive"))
    )
    (net (code "55") (name "Net-(D24-D)") (class "Default")
      (node (ref "D24") (pin "2") (pinfunction "D_2") (pintype "passive"))
      (node (ref "D25") (pin "2") (pinfunction "D_2") (pintype "passive"))
      (node (ref "D26") (pin "2") (pinfunction "D_2") (pintype "passive"))
      (node (ref "D27") (pin "2") (pinfunction "D_2") (pintype "passive"))
      (node (ref "D28") (pin "2") (pinfunction "D_2") (pintype "passive"))
    )
    (net (code "56") (name "Net-(D24-E)") (class "Default")
      (node (ref "D24") (pin "1") (pinfunction "E_1") (pintype "passive"))
      (node (ref "D25") (pin "1") (pinfunction "E_1") (pintype "passive"))
      (node (ref "D26") (pin "1") (pinfunction "E_1") (pintype "passive"))
      (node (ref "D27") (pin "1") (pinfunction "E_1") (pintype "passive"))
      (node (ref "D28") (pin "1") (pinfunction "E_1") (pintype "passive"))
    )
    (net (code "57") (name "Net-(D24-G)") (class "Default")
      (node (ref "D24") (pin "10") (pinfunction "G_10") (pintype "passive"))
      (node (ref "D25") (pin "10") (pinfunction "G_10") (pintype "passive"))
      (node (ref "D26") (pin "10") (pinfunction "G_10") (pintype "passive"))
      (node (ref "D27") (pin "10") (pinfunction "G_10") (pintype "passive"))
      (node (ref "D28") (pin "10") (pinfunction "G_10") (pintype "passive"))
    )
    (net (code "58") (name "Net-(D25-CK1)") (class "Default")
      (node (ref "D25") (pin "3") (pinfunction "CK1_3") (pintype "passive"))
      (node (ref "X4") (pin "1") (pinfunction "S_1") (pintype "passive"))
    )
    (net (code "59") (name "Net-(D26-CK1)") (class "Default")
      (node (ref "D26") (pin "3") (pinfunction "CK1_3") (pintype "passive"))
      (node (ref "X4") (pin "2") (pinfunction "S_2") (pintype "passive"))
    )
    (net (code "60") (name "Net-(D27-CK1)") (class "Default")
      (node (ref "D27") (pin "3") (pinfunction "CK1_3") (pintype "passive"))
      (node (ref "X4") (pin "3") (pinfunction "S_3") (pintype "passive"))
    )
    (net (code "61") (name "Net-(D28-CK1)") (class "Default")
      (node (ref "D28") (pin "3") (pinfunction "CK1_3") (pintype "passive"))
      (node (ref "X4") (pin "4") (pinfunction "S_4") (pintype "passive"))
    )
    (net (code "62") (name "Net-(D29-CK1)") (class "Default")
      (node (ref "D29") (pin "3") (pinfunction "CK1_3") (pintype "passive"))
      (node (ref "X4") (pin "5") (pinfunction "S_5") (pintype "passive"))
    )
    (net (code "63") (name "Net-(D29-DP)") (class "Default")
      (node (ref "D29") (pin "5") (pinfunction "DP_5") (pintype "passive"))
      (node (ref "D30") (pin "5") (pinfunction "DP_5") (pintype "passive"))
      (node (ref "D31") (pin "5") (pinfunction "DP_5") (pintype "passive"))
      (node (ref "D32") (pin "5") (pinfunction "DP_5") (pintype "passive"))
      (node (ref "D33") (pin "5") (pinfunction "DP_5") (pintype "passive"))
      (node (ref "D34") (pin "5") (pinfunction "DP_5") (pintype "passive"))
      (node (ref "D35") (pin "5") (pinfunction "DP_5") (pintype "passive"))
      (node (ref "D36") (pin "5") (pinfunction "DP_5") (pintype "passive"))
      (node (ref "D37") (pin "5") (pinfunction "DP_5") (pintype "passive"))
      (node (ref "D38") (pin "5") (pinfunction "DP_5") (pintype "passive"))
    )
    (net (code "64") (name "Net-(D29-F)") (class "Default")
      (node (ref "D29") (pin "9") (pinfunction "F_9") (pintype "passive"))
      (node (ref "D30") (pin "9") (pinfunction "F_9") (pintype "passive"))
      (node (ref "D31") (pin "9") (pinfunction "F_9") (pintype "passive"))
      (node (ref "D32") (pin "9") (pinfunction "F_9") (pintype "passive"))
      (node (ref "D33") (pin "9") (pinfunction "F_9") (pintype "passive"))
      (node (ref "D34") (pin "9") (pinfunction "F_9") (pintype "passive"))
      (node (ref "D35") (pin "9") (pinfunction "F_9") (pintype "passive"))
      (node (ref "D36") (pin "9") (pinfunction "F_9") (pintype "passive"))
      (node (ref "D37") (pin "9") (pinfunction "F_9") (pintype "passive"))
      (node (ref "D38") (pin "9") (pinfunction "F_9") (pintype "passive"))
    )
    (net (code "65") (name "Net-(D29-G)") (class "Default")
      (node (ref "D29") (pin "10") (pinfunction "G_10") (pintype "passive"))
      (node (ref "D30") (pin "10") (pinfunction "G_10") (pintype "passive"))
      (node (ref "D31") (pin "10") (pinfunction "G_10") (pintype "passive"))
      (node (ref "D32") (pin "10") (pinfunction "G_10") (pintype "passive"))
      (node (ref "D33") (pin "10") (pinfunction "G_10") (pintype "passive"))
    )
    (net (code "66") (name "Net-(D30-CK1)") (class "Default")
      (node (ref "D30") (pin "3") (pinfunction "CK1_3") (pintype "passive"))
      (node (ref "X4") (pin "6") (pinfunction "S_6") (pintype "passive"))
    )
    (net (code "67") (name "Net-(D31-A)") (class "Default")
      (node (ref "D31") (pin "7") (pinfunction "A_7") (pintype "passive"))
      (node (ref "D32") (pin "7") (pinfunction "A_7") (pintype "passive"))
      (node (ref "D33") (pin "7") (pinfunction "A_7") (pintype "passive"))
    )
    (net (code "68") (name "Net-(D31-B)") (class "Default")
      (node (ref "D31") (pin "6") (pinfunction "B_6") (pintype "passive"))
      (node (ref "D32") (pin "6") (pinfunction "B_6") (pintype "passive"))
      (node (ref "D33") (pin "6") (pinfunction "B_6") (pintype "passive"))
    )
    (net (code "69") (name "Net-(D31-C)") (class "Default")
      (node (ref "D31") (pin "4") (pinfunction "C_4") (pintype "passive"))
      (node (ref "D32") (pin "4") (pinfunction "C_4") (pintype "passive"))
      (node (ref "D33") (pin "4") (pinfunction "C_4") (pintype "passive"))
    )
    (net (code "70") (name "Net-(D31-CK1)") (class "Default")
      (node (ref "D31") (pin "3") (pinfunction "CK1_3") (pintype "passive"))
      (node (ref "X4") (pin "7") (pinfunction "S_7") (pintype "passive"))
    )
    (net (code "71") (name "Net-(D31-D)") (class "Default")
      (node (ref "D31") (pin "2") (pinfunction "D_2") (pintype "passive"))
      (node (ref "D32") (pin "2") (pinfunction "D_2") (pintype "passive"))
      (node (ref "D33") (pin "2") (pinfunction "D_2") (pintype "passive"))
    )
    (net (code "72") (name "Net-(D31-E)") (class "Default")
      (node (ref "D31") (pin "1") (pinfunction "E_1") (pintype "passive"))
      (node (ref "D32") (pin "1") (pinfunction "E_1") (pintype "passive"))
      (node (ref "D33") (pin "1") (pinfunction "E_1") (pintype "passive"))
    )
    (net (code "73") (name "Net-(D32-CK1)") (class "Default")
      (node (ref "D32") (pin "3") (pinfunction "CK1_3") (pintype "passive"))
      (node (ref "X4") (pin "8") (pinfunction "S_8") (pintype "passive"))
    )
    (net (code "74") (name "Net-(D33-CK1)") (class "Default")
      (node (ref "D33") (pin "3") (pinfunction "CK1_3") (pintype "passive"))
      (node (ref "X5") (pin "1") (pinfunction "S_1") (pintype "passive"))
    )
    (net (code "75") (name "Net-(D34-A)") (class "Default")
      (node (ref "D34") (pin "7") (pinfunction "A_7") (pintype "passive"))
      (node (ref "D35") (pin "7") (pinfunction "A_7") (pintype "passive"))
      (node (ref "D36") (pin "7") (pinfunction "A_7") (pintype "passive"))
      (node (ref "D37") (pin "7") (pinfunction "A_7") (pintype "passive"))
      (node (ref "D38") (pin "7") (pinfunction "A_7") (pintype "passive"))
    )
    (net (code "76") (name "Net-(D34-B)") (class "Default")
      (node (ref "D34") (pin "6") (pinfunction "B_6") (pintype "passive"))
      (node (ref "D35") (pin "6") (pinfunction "B_6") (pintype "passive"))
      (node (ref "D36") (pin "6") (pinfunction "B_6") (pintype "passive"))
      (node (ref "D37") (pin "6") (pinfunction "B_6") (pintype "passive"))
      (node (ref "D38") (pin "6") (pinfunction "B_6") (pintype "passive"))
    )
    (net (code "77") (name "Net-(D34-C)") (class "Default")
      (node (ref "D34") (pin "4") (pinfunction "C_4") (pintype "passive"))
      (node (ref "D35") (pin "4") (pinfunction "C_4") (pintype "passive"))
      (node (ref "D36") (pin "4") (pinfunction "C_4") (pintype "passive"))
      (node (ref "D37") (pin "4") (pinfunction "C_4") (pintype "passive"))
      (node (ref "D38") (pin "4") (pinfunction "C_4") (pintype "passive"))
    )
    (net (code "78") (name "Net-(D34-CK1)") (class "Default")
      (node (ref "D34") (pin "3") (pinfunction "CK1_3") (pintype "passive"))
      (node (ref "X5") (pin "2") (pinfunction "S_2") (pintype "passive"))
    )
    (net (code "79") (name "Net-(D34-D)") (class "Default")
      (node (ref "D34") (pin "2") (pinfunction "D_2") (pintype "passive"))
      (node (ref "D35") (pin "2") (pinfunction "D_2") (pintype "passive"))
      (node (ref "D36") (pin "2") (pinfunction "D_2") (pintype "passive"))
      (node (ref "D37") (pin "2") (pinfunction "D_2") (pintype "passive"))
      (node (ref "D38") (pin "2") (pinfunction "D_2") (pintype "passive"))
    )
    (net (code "80") (name "Net-(D34-E)") (class "Default")
      (node (ref "D34") (pin "1") (pinfunction "E_1") (pintype "passive"))
      (node (ref "D35") (pin "1") (pinfunction "E_1") (pintype "passive"))
      (node (ref "D36") (pin "1") (pinfunction "E_1") (pintype "passive"))
      (node (ref "D37") (pin "1") (pinfunction "E_1") (pintype "passive"))
      (node (ref "D38") (pin "1") (pinfunction "E_1") (pintype "passive"))
    )
    (net (code "81") (name "Net-(D34-G)") (class "Default")
      (node (ref "D34") (pin "10") (pinfunction "G_10") (pintype "passive"))
      (node (ref "D35") (pin "10") (pinfunction "G_10") (pintype "passive"))
      (node (ref "D36") (pin "10") (pinfunction "G_10") (pintype "passive"))
      (node (ref "D37") (pin "10") (pinfunction "G_10") (pintype "passive"))
      (node (ref "D38") (pin "10") (pinfunction "G_10") (pintype "passive"))
    )
    (net (code "82") (name "Net-(D35-CK1)") (class "Default")
      (node (ref "D35") (pin "3") (pinfunction "CK1_3") (pintype "passive"))
      (node (ref "X5") (pin "3") (pinfunction "S_3") (pintype "passive"))
    )
    (net (code "83") (name "Net-(D36-CK1)") (class "Default")
      (node (ref "D36") (pin "3") (pinfunction "CK1_3") (pintype "passive"))
      (node (ref "X5") (pin "4") (pinfunction "S_4") (pintype "passive"))
    )
    (net (code "84") (name "Net-(D37-CK1)") (class "Default")
      (node (ref "D37") (pin "3") (pinfunction "CK1_3") (pintype "passive"))
      (node (ref "X5") (pin "5") (pinfunction "S_5") (pintype "passive"))
    )
    (net (code "85") (name "Net-(D38-CK1)") (class "Default")
      (node (ref "D38") (pin "3") (pinfunction "CK1_3") (pintype "passive"))
      (node (ref "X5") (pin "6") (pinfunction "S_6") (pintype "passive"))
    )
    (net (code "86") (name "unconnected-(D1-CK2-Pad8)") (class "Default")
      (node (ref "D1") (pin "8") (pinfunction "CK2_8") (pintype "passive"))
    )
    (net (code "87") (name "unconnected-(D2-CK2-Pad8)") (class "Default")
      (node (ref "D2") (pin "8") (pinfunction "CK2_8") (pintype "passive"))
    )
    (net (code "88") (name "unconnected-(D3-CK2-Pad8)") (class "Default")
      (node (ref "D3") (pin "8") (pinfunction "CK2_8") (pintype "passive"))
    )
    (net (code "89") (name "unconnected-(D4-CK2-Pad8)") (class "Default")
      (node (ref "D4") (pin "8") (pinfunction "CK2_8") (pintype "passive"))
    )
    (net (code "90") (name "unconnected-(D5-CK2-Pad8)") (class "Default")
      (node (ref "D5") (pin "8") (pinfunction "CK2_8") (pintype "passive"))
    )
    (net (code "91") (name "unconnected-(D6-CK2-Pad8)") (class "Default")
      (node (ref "D6") (pin "8") (pinfunction "CK2_8") (pintype "passive"))
    )
    (net (code "92") (name "unconnected-(D7-CK2-Pad8)") (class "Default")
      (node (ref "D7") (pin "8") (pinfunction "CK2_8") (pintype "passive"))
    )
    (net (code "93") (name "unconnected-(D8-CK2-Pad8)") (class "Default")
      (node (ref "D8") (pin "8") (pinfunction "CK2_8") (pintype "passive"))
    )
    (net (code "94") (name "unconnected-(D9-CK2-Pad8)") (class "Default")
      (node (ref "D9") (pin "8") (pinfunction "CK2_8") (pintype "passive"))
    )
    (net (code "95") (name "unconnected-(D10-CK2-Pad8)") (class "Default")
      (node (ref "D10") (pin "8") (pinfunction "CK2_8") (pintype "passive"))
    )
    (net (code "96") (name "unconnected-(D11-CK2-Pad8)") (class "Default")
      (node (ref "D11") (pin "8") (pinfunction "CK2_8") (pintype "passive"))
    )
    (net (code "97") (name "unconnected-(D12-CK2-Pad8)") (class "Default")
      (node (ref "D12") (pin "8") (pinfunction "CK2_8") (pintype "passive"))
    )
    (net (code "98") (name "unconnected-(D13-CK2-Pad8)") (class "Default")
      (node (ref "D13") (pin "8") (pinfunction "CK2_8") (pintype "passive"))
    )
    (net (code "99") (name "unconnected-(D14-CK2-Pad8)") (class "Default")
      (node (ref "D14") (pin "8") (pinfunction "CK2_8") (pintype "passive"))
    )
    (net (code "100") (name "unconnected-(D15-CK2-Pad8)") (class "Default")
      (node (ref "D15") (pin "8") (pinfunction "CK2_8") (pintype "passive"))
    )
    (net (code "101") (name "unconnected-(D16-CK2-Pad8)") (class "Default")
      (node (ref "D16") (pin "8") (pinfunction "CK2_8") (pintype "passive"))
    )
    (net (code "102") (name "unconnected-(D17-CK2-Pad8)") (class "Default")
      (node (ref "D17") (pin "8") (pinfunction "CK2_8") (pintype "passive"))
    )
    (net (code "103") (name "unconnected-(D18-CK2-Pad8)") (class "Default")
      (node (ref "D18") (pin "8") (pinfunction "CK2_8") (pintype "passive"))
    )
    (net (code "104") (name "unconnected-(D19-CK2-Pad8)") (class "Default")
      (node (ref "D19") (pin "8") (pinfunction "CK2_8") (pintype "passive"))
    )
    (net (code "105") (name "unconnected-(D20-CK2-Pad8)") (class "Default")
      (node (ref "D20") (pin "8") (pinfunction "CK2_8") (pintype "passive"))
    )
    (net (code "106") (name "unconnected-(D21-CK2-Pad8)") (class "Default")
      (node (ref "D21") (pin "8") (pinfunction "CK2_8") (pintype "passive"))
    )
    (net (code "107") (name "unconnected-(D22-CK2-Pad8)") (class "Default")
      (node (ref "D22") (pin "8") (pinfunction "CK2_8") (pintype "passive"))
    )
    (net (code "108") (name "unconnected-(D23-CK2-Pad8)") (class "Default")
      (node (ref "D23") (pin "8") (pinfunction "CK2_8") (pintype "passive"))
    )
    (net (code "109") (name "unconnected-(D24-CK2-Pad8)") (class "Default")
      (node (ref "D24") (pin "8") (pinfunction "CK2_8") (pintype "passive"))
    )
    (net (code "110") (name "unconnected-(D25-CK2-Pad8)") (class "Default")
      (node (ref "D25") (pin "8") (pinfunction "CK2_8") (pintype "passive"))
    )
    (net (code "111") (name "unconnected-(D26-CK2-Pad8)") (class "Default")
      (node (ref "D26") (pin "8") (pinfunction "CK2_8") (pintype "passive"))
    )
    (net (code "112") (name "unconnected-(D27-CK2-Pad8)") (class "Default")
      (node (ref "D27") (pin "8") (pinfunction "CK2_8") (pintype "passive"))
    )
    (net (code "113") (name "unconnected-(D28-CK2-Pad8)") (class "Default")
      (node (ref "D28") (pin "8") (pinfunction "CK2_8") (pintype "passive"))
    )
    (net (code "114") (name "unconnected-(D29-CK2-Pad8)") (class "Default")
      (node (ref "D29") (pin "8") (pinfunction "CK2_8") (pintype "passive"))
    )
    (net (code "115") (name "unconnected-(D30-CK2-Pad8)") (class "Default")
      (node (ref "D30") (pin "8") (pinfunction "CK2_8") (pintype "passive"))
    )
    (net (code "116") (name "unconnected-(D31-CK2-Pad8)") (class "Default")
      (node (ref "D31") (pin "8") (pinfunction "CK2_8") (pintype "passive"))
    )
    (net (code "117") (name "unconnected-(D32-CK2-Pad8)") (class "Default")
      (node (ref "D32") (pin "8") (pinfunction "CK2_8") (pintype "passive"))
    )
    (net (code "118") (name "unconnected-(D33-CK2-Pad8)") (class "Default")
      (node (ref "D33") (pin "8") (pinfunction "CK2_8") (pintype "passive"))
    )
    (net (code "119") (name "unconnected-(D34-CK2-Pad8)") (class "Default")
      (node (ref "D34") (pin "8") (pinfunction "CK2_8") (pintype "passive"))
    )
    (net (code "120") (name "unconnected-(D35-CK2-Pad8)") (class "Default")
      (node (ref "D35") (pin "8") (pinfunction "CK2_8") (pintype "passive"))
    )
    (net (code "121") (name "unconnected-(D36-CK2-Pad8)") (class "Default")
      (node (ref "D36") (pin "8") (pinfunction "CK2_8") (pintype "passive"))
    )
    (net (code "122") (name "unconnected-(D37-CK2-Pad8)") (class "Default")
      (node (ref "D37") (pin "8") (pinfunction "CK2_8") (pintype "passive"))
    )
    (net (code "123") (name "unconnected-(D38-CK2-Pad8)") (class "Default")
      (node (ref "D38") (pin "8") (pinfunction "CK2_8") (pintype "passive"))
    )
    (net (code "124") (name "unconnected-(X5G-S-Pad7)") (class "Default")
      (node (ref "X5") (pin "7") (pinfunction "S_7") (pintype "passive"))
    )
    (net (code "125") (name "unconnected-(X5H-S-Pad8)") (class "Default")
      (node (ref "X5") (pin "8") (pinfunction "S_8") (pintype "passive"))
    )
  )
)
